# PowerSplitter.net
KiCad netlist of a schematic drawn in Altium Designer
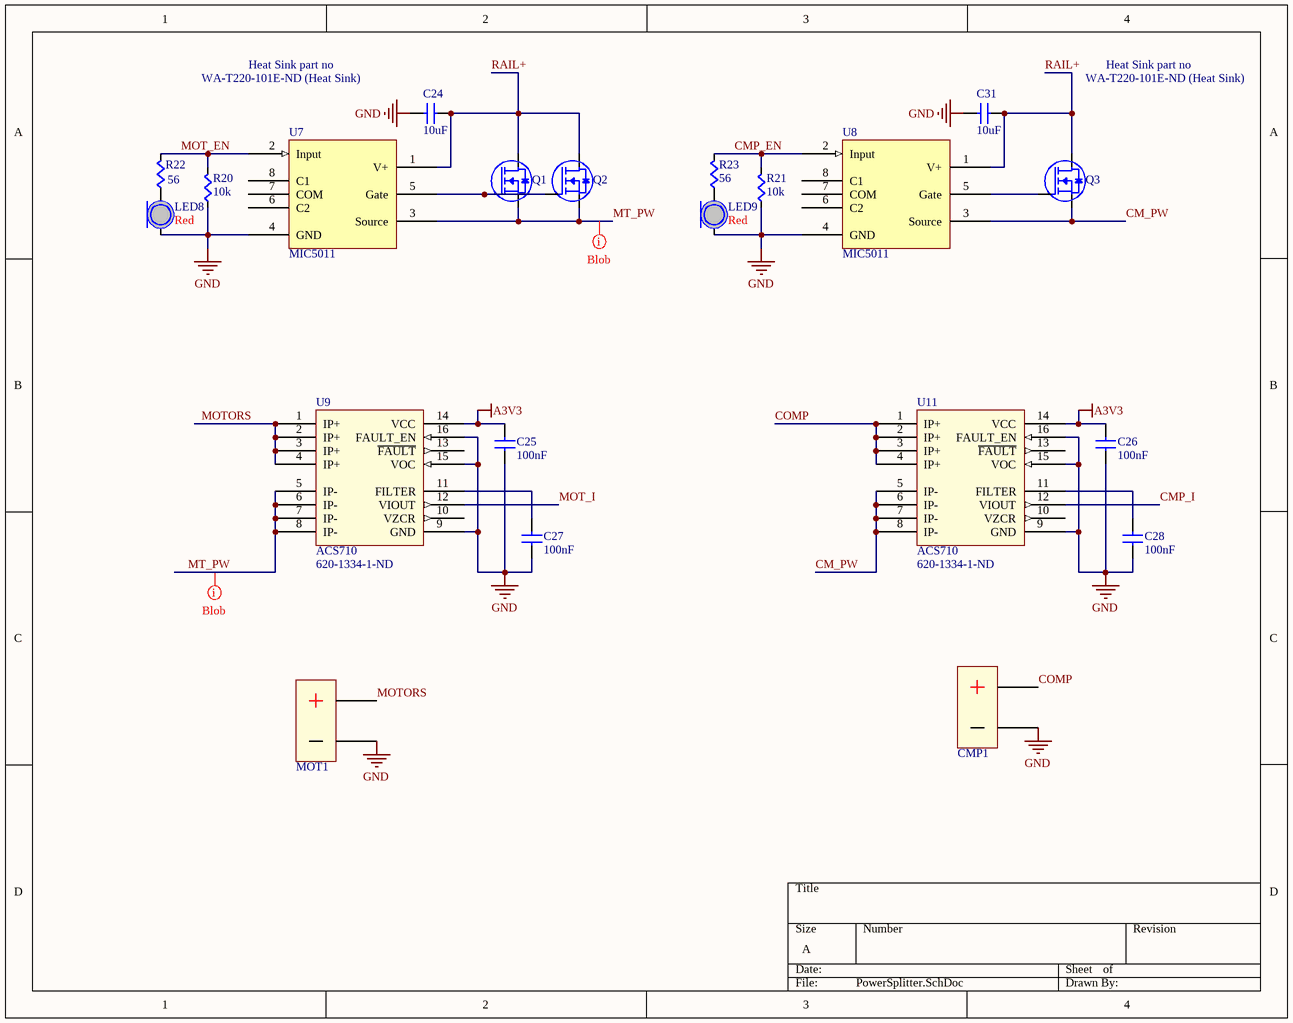
[diagram p0: PowerSplitter.SchDoc]

(export (version "E")
  (design (tool "Eeschema 10.0.6"))
  (components
    (comp (ref "C24")
      (value "10uF")
      (footprint "CAPC1206")
      (fields (field (name "Comment") "Cap"))
      (libsource (lib "SubjuGator8") (part "Cap"))
    )
    (comp (ref "C25")
      (value "100nF")
      (footprint "CAPC0603")
      (fields (field (name "Comment") "Cap"))
      (libsource (lib "SubjuGator8") (part "Cap"))
    )
    (comp (ref "C26")
      (value "100nF")
      (footprint "CAPC0603")
      (fields (field (name "Comment") "Cap"))
      (libsource (lib "SubjuGator8") (part "Cap"))
    )
    (comp (ref "C27")
      (value "100nF")
      (footprint "CAPC0603")
      (fields (field (name "Comment") "Cap"))
      (libsource (lib "SubjuGator8") (part "Cap"))
    )
    (comp (ref "C28")
      (value "100nF")
      (footprint "CAPC0603")
      (fields (field (name "Comment") "Cap"))
      (libsource (lib "SubjuGator8") (part "Cap"))
    )
    (comp (ref "C31")
      (value "10uF")
      (footprint "CAPC1206")
      (fields (field (name "Comment") "Cap"))
      (libsource (lib "SubjuGator8") (part "Cap"))
    )
    (comp (ref "CMP1")
      (value "BATWIRE")
      (footprint "BATWIRE12")
      (description "Two large gauge leads soldered directly to the board.")
      (libsource (lib "SubjuGator8") (part "BATWIRE"))
    )
    (comp (ref "LED8")
      (value "LED")
      (footprint "LED0805")
      (fields (field (name "COLOR") "Red"))
      (libsource (lib "SubjuGator8") (part "LED"))
    )
    (comp (ref "LED9")
      (value "LED")
      (footprint "LED0805")
      (fields (field (name "COLOR") "Red"))
      (libsource (lib "SubjuGator8") (part "LED"))
    )
    (comp (ref "MOT1")
      (value "BATWIRE")
      (footprint "BATWIRE12")
      (description "Two large gauge leads soldered directly to the board.")
      (libsource (lib "SubjuGator8") (part "BATWIRE"))
    )
    (comp (ref "Q1")
      (value "IRFB3306PbF")
      (footprint "TO-220AB Heatsink Vertical")
      (description "HEXFET Power MOSFET")
      (libsource (lib "SubjuGator8") (part "IRFx3306PbF"))
    )
    (comp (ref "Q2")
      (value "IRFB3306PbF")
      (footprint "TO-220AB Heatsink Vertical")
      (description "HEXFET Power MOSFET")
      (libsource (lib "SubjuGator8") (part "IRFx3306PbF"))
    )
    (comp (ref "Q3")
      (value "IRFB3306PbF")
      (footprint "TO-220AB Heatsink Vertical")
      (description "HEXFET Power MOSFET")
      (libsource (lib "SubjuGator8") (part "IRFx3306PbF"))
    )
    (comp (ref "R20")
      (value "10k")
      (footprint "RES0603")
      (fields (field (name "Comment") "Res"))
      (libsource (lib "SubjuGator8") (part "Res"))
    )
    (comp (ref "R21")
      (value "10k")
      (footprint "RES0603")
      (fields (field (name "Comment") "Res"))
      (libsource (lib "SubjuGator8") (part "Res"))
    )
    (comp (ref "R22")
      (value "56")
      (footprint "RES0603")
      (fields (field (name "Comment") "Res"))
      (libsource (lib "SubjuGator8") (part "Res"))
    )
    (comp (ref "R23")
      (value "56")
      (footprint "RES0603")
      (fields (field (name "Comment") "Res"))
      (libsource (lib "SubjuGator8") (part "Res"))
    )
    (comp (ref "U7")
      (value "MIC5011")
      (footprint "MIC5011")
      (description "Minimum Parts High- or Low-Side MOSFET Driver")
      (libsource (lib "SubjuGator8") (part "MIC5011"))
    )
    (comp (ref "U8")
      (value "MIC5011")
      (footprint "MIC5011")
      (description "Minimum Parts High- or Low-Side MOSFET Driver")
      (libsource (lib "SubjuGator8") (part "MIC5011"))
    )
    (comp (ref "U9")
      (value "ACS710")
      (footprint "ACS710")
      (description "Current Sensor with Integrated Overcurrent Detection")
      (fields (field (name "SUPPLIER PART NUMBER 1") "620-1334-1-ND"))
      (libsource (lib "SubjuGator8") (part "ACS710"))
    )
    (comp (ref "U11")
      (value "ACS710")
      (footprint "ACS710")
      (description "Current Sensor with Integrated Overcurrent Detection")
      (fields (field (name "SUPPLIER PART NUMBER 1") "620-1334-1-ND"))
      (libsource (lib "SubjuGator8") (part "ACS710"))
    )
  )
  (nets
    (net (code "1") (name "/CMP_EN") (class "Default")
      (node (ref "R21") (pin "1") (pinfunction "A_1") (pintype "passive"))
      (node (ref "R23") (pin "1") (pinfunction "A_1") (pintype "passive"))
      (node (ref "U8") (pin "2") (pinfunction "Input_2") (pintype "input"))
    )
    (net (code "2") (name "/CMP_I") (class "Default")
      (node (ref "U11") (pin "12") (pinfunction "VIOUT_12") (pintype "output"))
    )
    (net (code "3") (name "/CM_PW") (class "Default")
      (node (ref "Q3") (pin "S") (pinfunction "S_S") (pintype "passive"))
      (node (ref "U11") (pin "5") (pinfunction "IP-_5") (pintype "passive"))
      (node (ref "U11") (pin "6") (pinfunction "IP-_6") (pintype "passive"))
      (node (ref "U11") (pin "7") (pinfunction "IP-_7") (pintype "passive"))
      (node (ref "U11") (pin "8") (pinfunction "IP-_8") (pintype "passive"))
      (node (ref "U8") (pin "3") (pinfunction "Source_3") (pintype "passive"))
    )
    (net (code "4") (name "/COMP") (class "Default")
      (node (ref "CMP1") (pin "+") (pinfunction "+_+") (pintype "power_in"))
      (node (ref "U11") (pin "1") (pinfunction "IP+_1") (pintype "passive"))
      (node (ref "U11") (pin "2") (pinfunction "IP+_2") (pintype "passive"))
      (node (ref "U11") (pin "3") (pinfunction "IP+_3") (pintype "passive"))
      (node (ref "U11") (pin "4") (pinfunction "IP+_4") (pintype "passive"))
    )
    (net (code "5") (name "/MOTORS") (class "Default")
      (node (ref "MOT1") (pin "+") (pinfunction "+_+") (pintype "power_in"))
      (node (ref "U9") (pin "1") (pinfunction "IP+_1") (pintype "passive"))
      (node (ref "U9") (pin "2") (pinfunction "IP+_2") (pintype "passive"))
      (node (ref "U9") (pin "3") (pinfunction "IP+_3") (pintype "passive"))
      (node (ref "U9") (pin "4") (pinfunction "IP+_4") (pintype "passive"))
    )
    (net (code "6") (name "/MOT_EN") (class "Default")
      (node (ref "R20") (pin "1") (pinfunction "A_1") (pintype "passive"))
      (node (ref "R22") (pin "1") (pinfunction "A_1") (pintype "passive"))
      (node (ref "U7") (pin "2") (pinfunction "Input_2") (pintype "input"))
    )
    (net (code "7") (name "/MOT_I") (class "Default")
      (node (ref "U9") (pin "12") (pinfunction "VIOUT_12") (pintype "output"))
    )
    (net (code "8") (name "/MT_PW") (class "Default")
      (node (ref "Q1") (pin "S") (pinfunction "S_S") (pintype "passive"))
      (node (ref "Q2") (pin "S") (pinfunction "S_S") (pintype "passive"))
      (node (ref "U7") (pin "3") (pinfunction "Source_3") (pintype "passive"))
      (node (ref "U9") (pin "5") (pinfunction "IP-_5") (pintype "passive"))
      (node (ref "U9") (pin "6") (pinfunction "IP-_6") (pintype "passive"))
      (node (ref "U9") (pin "7") (pinfunction "IP-_7") (pintype "passive"))
      (node (ref "U9") (pin "8") (pinfunction "IP-_8") (pintype "passive"))
    )
    (net (code "9") (name "/RAIL+") (class "Default")
      (node (ref "C24") (pin "2") (pinfunction "B_2") (pintype "passive"))
      (node (ref "C31") (pin "2") (pinfunction "B_2") (pintype "passive"))
      (node (ref "Q1") (pin "D") (pinfunction "D_D") (pintype "passive"))
      (node (ref "Q2") (pin "D") (pinfunction "D_D") (pintype "passive"))
      (node (ref "Q3") (pin "D") (pinfunction "D_D") (pintype "passive"))
      (node (ref "U7") (pin "1") (pinfunction "V+_1") (pintype "power_in"))
      (node (ref "U8") (pin "1") (pinfunction "V+_1") (pintype "power_in"))
    )
    (net (code "10") (name "A3V3") (class "Default")
      (node (ref "C25") (pin "1") (pinfunction "A_1") (pintype "passive"))
      (node (ref "C26") (pin "1") (pinfunction "A_1") (pintype "passive"))
      (node (ref "U11") (pin "14") (pinfunction "VCC_14") (pintype "power_in"))
      (node (ref "U9") (pin "14") (pinfunction "VCC_14") (pintype "power_in"))
    )
    (net (code "11") (name "GND") (class "Default")
      (node (ref "C24") (pin "1") (pinfunction "A_1") (pintype "passive"))
      (node (ref "C25") (pin "2") (pinfunction "B_2") (pintype "passive"))
      (node (ref "C26") (pin "2") (pinfunction "B_2") (pintype "passive"))
      (node (ref "C27") (pin "2") (pinfunction "B_2") (pintype "passive"))
      (node (ref "C28") (pin "2") (pinfunction "B_2") (pintype "passive"))
      (node (ref "C31") (pin "1") (pinfunction "A_1") (pintype "passive"))
      (node (ref "CMP1") (pin "-") (pinfunction "-_-") (pintype "power_in"))
      (node (ref "LED8") (pin "C") (pinfunction "C_C") (pintype "passive"))
      (node (ref "LED9") (pin "C") (pinfunction "C_C") (pintype "passive"))
      (node (ref "MOT1") (pin "-") (pinfunction "-_-") (pintype "power_in"))
      (node (ref "R20") (pin "2") (pinfunction "B_2") (pintype "passive"))
      (node (ref "R21") (pin "2") (pinfunction "B_2") (pintype "passive"))
      (node (ref "U11") (pin "15") (pinfunction "VOC_15") (pintype "input"))
      (node (ref "U11") (pin "16") (pinfunction "FAULT_EN_16") (pintype "input"))
      (node (ref "U11") (pin "9") (pinfunction "GND_9") (pintype "power_in"))
      (node (ref "U7") (pin "4") (pinfunction "GND_4") (pintype "power_in"))
      (node (ref "U8") (pin "4") (pinfunction "GND_4") (pintype "power_in"))
      (node (ref "U9") (pin "15") (pinfunction "VOC_15") (pintype "input"))
      (node (ref "U9") (pin "16") (pinfunction "FAULT_EN_16") (pintype "input"))
      (node (ref "U9") (pin "9") (pinfunction "GND_9") (pintype "power_in"))
    )
    (net (code "12") (name "Net-(C27-A)") (class "Default")
      (node (ref "C27") (pin "1") (pinfunction "A_1") (pintype "passive"))
      (node (ref "U9") (pin "11") (pinfunction "FILTER_11") (pintype "passive"))
    )
    (net (code "13") (name "Net-(C28-A)") (class "Default")
      (node (ref "C28") (pin "1") (pinfunction "A_1") (pintype "passive"))
      (node (ref "U11") (pin "11") (pinfunction "FILTER_11") (pintype "passive"))
    )
    (net (code "14") (name "Net-(R22-B)") (class "Default")
      (node (ref "LED8") (pin "A") (pinfunction "A_A") (pintype "passive"))
      (node (ref "R22") (pin "2") (pinfunction "B_2") (pintype "passive"))
    )
    (net (code "15") (name "Net-(R23-B)") (class "Default")
      (node (ref "LED9") (pin "A") (pinfunction "A_A") (pintype "passive"))
      (node (ref "R23") (pin "2") (pinfunction "B_2") (pintype "passive"))
    )
    (net (code "16") (name "Net-(U7-Gate)") (class "Default")
      (node (ref "Q1") (pin "G") (pinfunction "G_G") (pintype "passive"))
      (node (ref "Q2") (pin "G") (pinfunction "G_G") (pintype "passive"))
      (node (ref "U7") (pin "5") (pinfunction "Gate_5") (pintype "passive"))
    )
    (net (code "17") (name "Net-(U8-Gate)") (class "Default")
      (node (ref "Q3") (pin "G") (pinfunction "G_G") (pintype "passive"))
      (node (ref "U8") (pin "5") (pinfunction "Gate_5") (pintype "passive"))
    )
    (net (code "18") (name "unconnected-(U7-C1-Pad8)") (class "Default")
      (node (ref "U7") (pin "8") (pinfunction "C1_8") (pintype "passive"))
    )
    (net (code "19") (name "unconnected-(U7-C2-Pad6)") (class "Default")
      (node (ref "U7") (pin "6") (pinfunction "C2_6") (pintype "passive"))
    )
    (net (code "20") (name "unconnected-(U7-COM-Pad7)") (class "Default")
      (node (ref "U7") (pin "7") (pinfunction "COM_7") (pintype "passive"))
    )
    (net (code "21") (name "unconnected-(U8-C1-Pad8)") (class "Default")
      (node (ref "U8") (pin "8") (pinfunction "C1_8") (pintype "passive"))
    )
    (net (code "22") (name "unconnected-(U8-C2-Pad6)") (class "Default")
      (node (ref "U8") (pin "6") (pinfunction "C2_6") (pintype "passive"))
    )
    (net (code "23") (name "unconnected-(U8-COM-Pad7)") (class "Default")
      (node (ref "U8") (pin "7") (pinfunction "COM_7") (pintype "passive"))
    )
    (net (code "24") (name "unconnected-(U9-VZCR-Pad10)") (class "Default")
      (node (ref "U9") (pin "10") (pinfunction "VZCR_10") (pintype "output"))
    )
    (net (code "25") (name "unconnected-(U9-~{FAULT}-Pad13)") (class "Default")
      (node (ref "U9") (pin "13") (pinfunction "~{FAULT}_13") (pintype "output"))
    )
    (net (code "26") (name "unconnected-(U11-VZCR-Pad10)") (class "Default")
      (node (ref "U11") (pin "10") (pinfunction "VZCR_10") (pintype "output"))
    )
    (net (code "27") (name "unconnected-(U11-~{FAULT}-Pad13)") (class "Default")
      (node (ref "U11") (pin "13") (pinfunction "~{FAULT}_13") (pintype "output"))
    )
  )
)
